# OUTL.net
KiCad netlist of a schematic drawn in Altium Designer
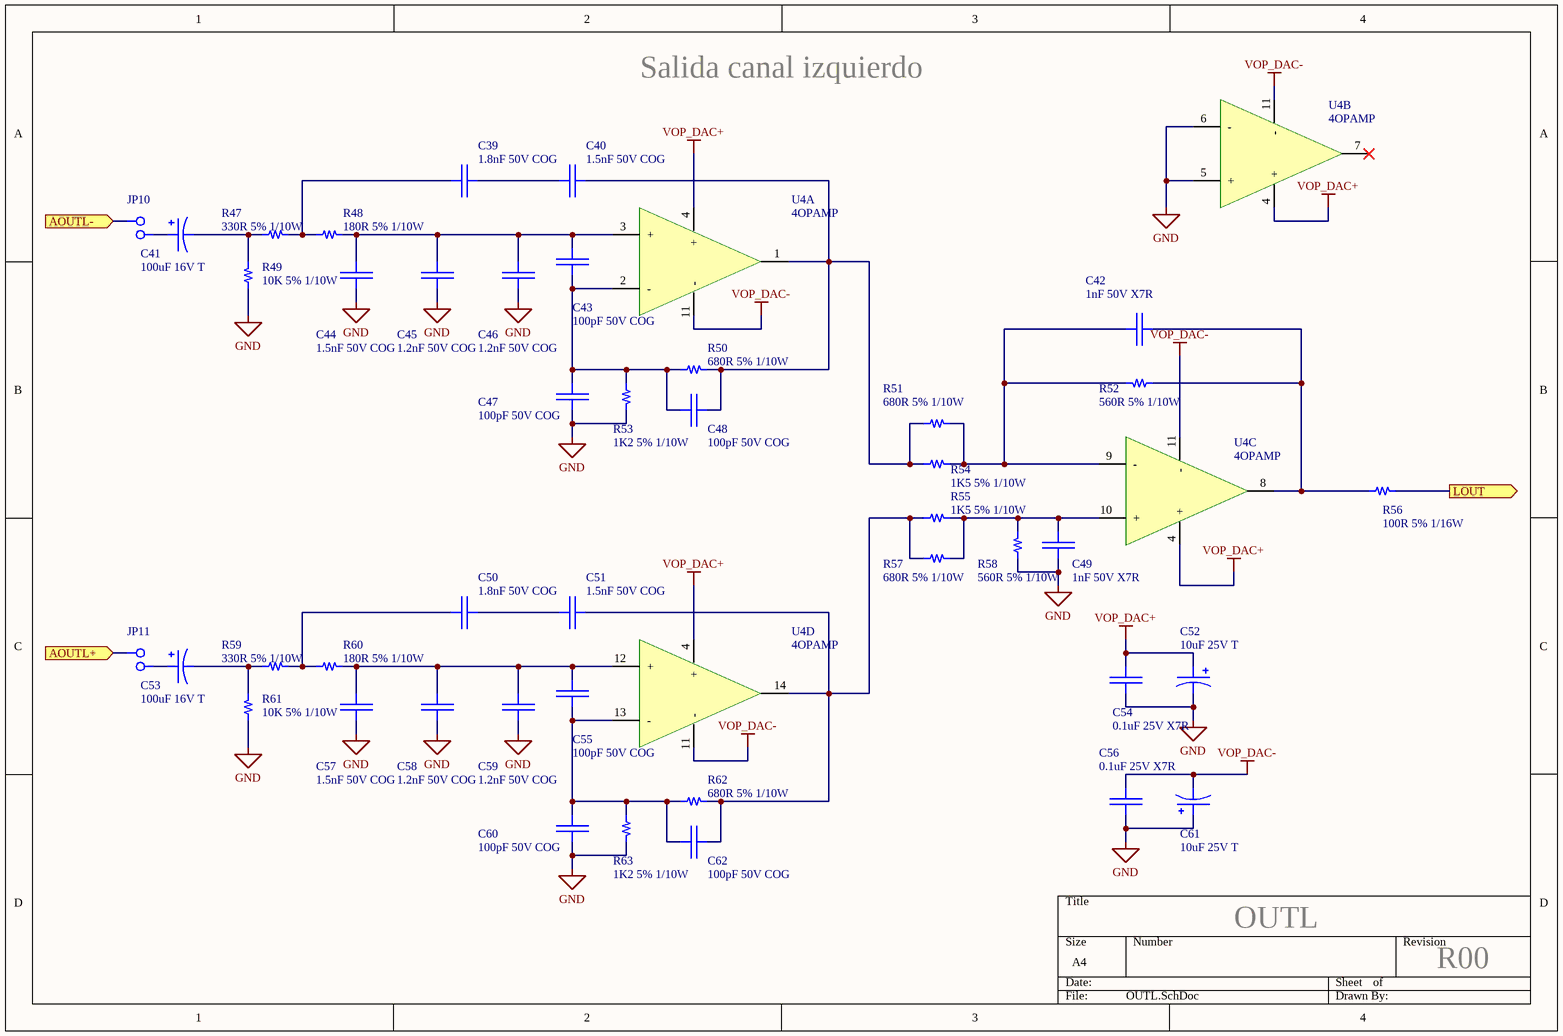
[diagram p0: OUTL.SchDoc]

(export (version "E")
  (design (tool "Eeschema 10.0.6"))
  (components
    (comp (ref "C39")
      (value "1.8nF 50V COG")
      (footprint "C_0805")
      (description "Capacitor de placas paralelas")
      (libsource (lib "Radios_Comunitarias") (part "Capacitor"))
    )
    (comp (ref "C40")
      (value "1.5nF 50V COG")
      (footprint "C_0805")
      (description "Capacitor de placas paralelas")
      (libsource (lib "Radios_Comunitarias") (part "Capacitor"))
    )
    (comp (ref "C41")
      (value "100uF 16V T")
      (footprint "TANT")
      (description "Capacitor polarizado")
      (libsource (lib "Radios_Comunitarias") (part "CapaPol"))
    )
    (comp (ref "C42")
      (value "1nF 50V X7R")
      (footprint "C_0805")
      (description "Capacitor de placas paralelas")
      (libsource (lib "Radios_Comunitarias") (part "Capacitor"))
    )
    (comp (ref "C43")
      (value "100pF 50V COG")
      (footprint "C_0805")
      (description "Capacitor de placas paralelas")
      (libsource (lib "Radios_Comunitarias") (part "Capacitor"))
    )
    (comp (ref "C44")
      (value "1.5nF 50V COG")
      (footprint "C_0805")
      (description "Capacitor de placas paralelas")
      (libsource (lib "Radios_Comunitarias") (part "Capacitor"))
    )
    (comp (ref "C45")
      (value "1.2nF 50V COG")
      (footprint "C_0805")
      (description "Capacitor de placas paralelas")
      (libsource (lib "Radios_Comunitarias") (part "Capacitor"))
    )
    (comp (ref "C46")
      (value "1.2nF 50V COG")
      (footprint "C_0805")
      (description "Capacitor de placas paralelas")
      (libsource (lib "Radios_Comunitarias") (part "Capacitor"))
    )
    (comp (ref "C47")
      (value "100pF 50V COG")
      (footprint "C_0805")
      (description "Capacitor de placas paralelas")
      (libsource (lib "Radios_Comunitarias") (part "Capacitor"))
    )
    (comp (ref "C48")
      (value "100pF 50V COG")
      (footprint "C_0805")
      (description "Capacitor de placas paralelas")
      (libsource (lib "Radios_Comunitarias") (part "Capacitor"))
    )
    (comp (ref "C49")
      (value "1nF 50V X7R")
      (footprint "C_0805")
      (description "Capacitor de placas paralelas")
      (libsource (lib "Radios_Comunitarias") (part "Capacitor"))
    )
    (comp (ref "C50")
      (value "1.8nF 50V COG")
      (footprint "C_0805")
      (description "Capacitor de placas paralelas")
      (libsource (lib "Radios_Comunitarias") (part "Capacitor"))
    )
    (comp (ref "C51")
      (value "1.5nF 50V COG")
      (footprint "C_0805")
      (description "Capacitor de placas paralelas")
      (libsource (lib "Radios_Comunitarias") (part "Capacitor"))
    )
    (comp (ref "C52")
      (value "10uF 25V T")
      (footprint "TANT")
      (description "Capacitor polarizado")
      (libsource (lib "") (part "CapaPol_1"))
    )
    (comp (ref "C53")
      (value "100uF 16V T")
      (footprint "TANT")
      (description "Capacitor polarizado")
      (libsource (lib "Radios_Comunitarias") (part "CapaPol"))
    )
    (comp (ref "C54")
      (value "0.1uF 25V X7R")
      (footprint "C_0805")
      (description "Capacitor de placas paralelas")
      (libsource (lib "Radios_Comunitarias") (part "Capacitor"))
    )
    (comp (ref "C55")
      (value "100pF 50V COG")
      (footprint "C_0805")
      (description "Capacitor de placas paralelas")
      (libsource (lib "Radios_Comunitarias") (part "Capacitor"))
    )
    (comp (ref "C56")
      (value "0.1uF 25V X7R")
      (footprint "C_0805")
      (description "Capacitor de placas paralelas")
      (libsource (lib "Radios_Comunitarias") (part "Capacitor"))
    )
    (comp (ref "C57")
      (value "1.5nF 50V COG")
      (footprint "C_0805")
      (description "Capacitor de placas paralelas")
      (libsource (lib "Radios_Comunitarias") (part "Capacitor"))
    )
    (comp (ref "C58")
      (value "1.2nF 50V COG")
      (footprint "C_0805")
      (description "Capacitor de placas paralelas")
      (libsource (lib "Radios_Comunitarias") (part "Capacitor"))
    )
    (comp (ref "C59")
      (value "1.2nF 50V COG")
      (footprint "C_0805")
      (description "Capacitor de placas paralelas")
      (libsource (lib "Radios_Comunitarias") (part "Capacitor"))
    )
    (comp (ref "C60")
      (value "100pF 50V COG")
      (footprint "C_0805")
      (description "Capacitor de placas paralelas")
      (libsource (lib "Radios_Comunitarias") (part "Capacitor"))
    )
    (comp (ref "C61")
      (value "10uF 25V T")
      (footprint "TANT")
      (description "Capacitor polarizado")
      (libsource (lib "") (part "CapaPol_1"))
    )
    (comp (ref "C62")
      (value "100pF 50V COG")
      (footprint "C_0805")
      (description "Capacitor de placas paralelas")
      (libsource (lib "Radios_Comunitarias") (part "Capacitor"))
    )
    (comp (ref "JP10")
      (value "Jumper 2x1")
      (footprint "Conn_2_1")
      (libsource (lib "Radios_Comunitarias") (part "Jumper 2x1"))
    )
    (comp (ref "JP11")
      (value "Jumper 2x1")
      (footprint "Conn_2_1")
      (libsource (lib "Radios_Comunitarias") (part "Jumper 2x1"))
    )
    (comp (ref "R47")
      (value "330R 5% 1/10W")
      (footprint "R_0805")
      (description "Resistencia")
      (libsource (lib "Radios_Comunitarias") (part "Resistor"))
    )
    (comp (ref "R48")
      (value "180R 5% 1/10W")
      (footprint "R_0805")
      (description "Resistencia")
      (libsource (lib "Radios_Comunitarias") (part "Resistor"))
    )
    (comp (ref "R49")
      (value "10K 5% 1/10W")
      (footprint "R_0805")
      (description "Resistencia")
      (libsource (lib "Radios_Comunitarias") (part "Resistor"))
    )
    (comp (ref "R50")
      (value "680R 5% 1/10W")
      (footprint "R_0805")
      (description "Resistencia")
      (libsource (lib "Radios_Comunitarias") (part "Resistor"))
    )
    (comp (ref "R51")
      (value "680R 5% 1/10W")
      (footprint "R_0805")
      (description "Resistencia")
      (libsource (lib "Radios_Comunitarias") (part "Resistor"))
    )
    (comp (ref "R52")
      (value "560R 5% 1/10W")
      (footprint "R_0805")
      (description "Resistencia")
      (libsource (lib "Radios_Comunitarias") (part "Resistor"))
    )
    (comp (ref "R53")
      (value "1K2 5% 1/10W")
      (footprint "R_0805")
      (description "Resistencia")
      (libsource (lib "Radios_Comunitarias") (part "Resistor"))
    )
    (comp (ref "R54")
      (value "1K5 5% 1/10W")
      (footprint "R_0805")
      (description "Resistencia")
      (libsource (lib "Radios_Comunitarias") (part "Resistor"))
    )
    (comp (ref "R55")
      (value "1K5 5% 1/10W")
      (footprint "R_0805")
      (description "Resistencia")
      (libsource (lib "Radios_Comunitarias") (part "Resistor"))
    )
    (comp (ref "R56")
      (value "100R 5% 1/16W")
      (footprint "R_0805")
      (description "Resistencia")
      (libsource (lib "Radios_Comunitarias") (part "Resistor"))
    )
    (comp (ref "R57")
      (value "680R 5% 1/10W")
      (footprint "R_0805")
      (description "Resistencia")
      (libsource (lib "Radios_Comunitarias") (part "Resistor"))
    )
    (comp (ref "R58")
      (value "560R 5% 1/10W")
      (footprint "R_0805")
      (description "Resistencia")
      (libsource (lib "Radios_Comunitarias") (part "Resistor"))
    )
    (comp (ref "R59")
      (value "330R 5% 1/10W")
      (footprint "R_0805")
      (description "Resistencia")
      (libsource (lib "Radios_Comunitarias") (part "Resistor"))
    )
    (comp (ref "R60")
      (value "180R 5% 1/10W")
      (footprint "R_0805")
      (description "Resistencia")
      (libsource (lib "Radios_Comunitarias") (part "Resistor"))
    )
    (comp (ref "R61")
      (value "10K 5% 1/10W")
      (footprint "R_0805")
      (description "Resistencia")
      (libsource (lib "Radios_Comunitarias") (part "Resistor"))
    )
    (comp (ref "R62")
      (value "680R 5% 1/10W")
      (footprint "R_0805")
      (description "Resistencia")
      (libsource (lib "Radios_Comunitarias") (part "Resistor"))
    )
    (comp (ref "R63")
      (value "1K2 5% 1/10W")
      (footprint "R_0805")
      (description "Resistencia")
      (libsource (lib "Radios_Comunitarias") (part "Resistor"))
    )
    (comp (ref "U4")
      (value "4OPAMP")
      (footprint "SOIC14")
      (description "Integrado con 4 operacionales")
      (libsource (lib "Radios_Comunitarias") (part "4OPAMP"))
    )
  )
  (nets
    (net (code "1") (name "/AOUTL+") (class "Default")
      (node (ref "JP11") (pin "1") (pinfunction "1_1") (pintype "passive"))
    )
    (net (code "2") (name "/AOUTL-") (class "Default")
      (node (ref "JP10") (pin "1") (pinfunction "1_1") (pintype "passive"))
    )
    (net (code "3") (name "/LOUT") (class "Default")
      (node (ref "R56") (pin "2") (pinfunction "2_2") (pintype "passive"))
    )
    (net (code "4") (name "GND") (class "Default")
      (node (ref "C44") (pin "1") (pinfunction "1_1") (pintype "passive"))
      (node (ref "C45") (pin "1") (pinfunction "1_1") (pintype "passive"))
      (node (ref "C46") (pin "1") (pinfunction "1_1") (pintype "passive"))
      (node (ref "C47") (pin "2") (pinfunction "2_2") (pintype "passive"))
      (node (ref "C49") (pin "2") (pinfunction "2_2") (pintype "passive"))
      (node (ref "C52") (pin "2") (pinfunction "2_2") (pintype "passive"))
      (node (ref "C54") (pin "2") (pinfunction "2_2") (pintype "passive"))
      (node (ref "C56") (pin "2") (pinfunction "2_2") (pintype "passive"))
      (node (ref "C57") (pin "1") (pinfunction "1_1") (pintype "passive"))
      (node (ref "C58") (pin "1") (pinfunction "1_1") (pintype "passive"))
      (node (ref "C59") (pin "1") (pinfunction "1_1") (pintype "passive"))
      (node (ref "C60") (pin "2") (pinfunction "2_2") (pintype "passive"))
      (node (ref "C61") (pin "1") (pinfunction "1_1") (pintype "passive"))
      (node (ref "R49") (pin "1") (pinfunction "1_1") (pintype "passive"))
      (node (ref "R53") (pin "2") (pinfunction "2_2") (pintype "passive"))
      (node (ref "R58") (pin "1") (pinfunction "1_1") (pintype "passive"))
      (node (ref "R61") (pin "1") (pinfunction "1_1") (pintype "passive"))
      (node (ref "R63") (pin "2") (pinfunction "2_2") (pintype "passive"))
      (node (ref "U4") (pin "5") (pinfunction "+_5") (pintype "passive"))
      (node (ref "U4") (pin "6") (pinfunction "-_6") (pintype "passive"))
    )
    (net (code "5") (name "Net-(C39-Pad1)") (class "Default")
      (node (ref "C39") (pin "1") (pinfunction "1_1") (pintype "passive"))
      (node (ref "C40") (pin "2") (pinfunction "2_2") (pintype "passive"))
    )
    (net (code "6") (name "Net-(C39-Pad2)") (class "Default")
      (node (ref "C39") (pin "2") (pinfunction "2_2") (pintype "passive"))
      (node (ref "R47") (pin "2") (pinfunction "2_2") (pintype "passive"))
      (node (ref "R48") (pin "1") (pinfunction "1_1") (pintype "passive"))
    )
    (net (code "7") (name "Net-(C41-Pad1)") (class "Default")
      (node (ref "C41") (pin "1") (pinfunction "1_1") (pintype "passive"))
      (node (ref "JP10") (pin "2") (pinfunction "2_2") (pintype "passive"))
    )
    (net (code "8") (name "Net-(C41-Pad2)") (class "Default")
      (node (ref "C41") (pin "2") (pinfunction "2_2") (pintype "passive"))
      (node (ref "R47") (pin "1") (pinfunction "1_1") (pintype "passive"))
      (node (ref "R49") (pin "2") (pinfunction "2_2") (pintype "passive"))
    )
    (net (code "9") (name "Net-(C42-Pad1)") (class "Default")
      (node (ref "C42") (pin "1") (pinfunction "1_1") (pintype "passive"))
      (node (ref "R51") (pin "2") (pinfunction "2_2") (pintype "passive"))
      (node (ref "R52") (pin "2") (pinfunction "2_2") (pintype "passive"))
      (node (ref "R54") (pin "2") (pinfunction "2_2") (pintype "passive"))
      (node (ref "U4") (pin "9") (pinfunction "-_9") (pintype "passive"))
    )
    (net (code "10") (name "Net-(C43-Pad1)") (class "Default")
      (node (ref "C43") (pin "1") (pinfunction "1_1") (pintype "passive"))
      (node (ref "C44") (pin "2") (pinfunction "2_2") (pintype "passive"))
      (node (ref "C45") (pin "2") (pinfunction "2_2") (pintype "passive"))
      (node (ref "C46") (pin "2") (pinfunction "2_2") (pintype "passive"))
      (node (ref "R48") (pin "2") (pinfunction "2_2") (pintype "passive"))
      (node (ref "U4") (pin "3") (pinfunction "+_3") (pintype "passive"))
    )
    (net (code "11") (name "Net-(C43-Pad2)") (class "Default")
      (node (ref "C43") (pin "2") (pinfunction "2_2") (pintype "passive"))
      (node (ref "C47") (pin "1") (pinfunction "1_1") (pintype "passive"))
      (node (ref "C48") (pin "1") (pinfunction "1_1") (pintype "passive"))
      (node (ref "R50") (pin "1") (pinfunction "1_1") (pintype "passive"))
      (node (ref "R53") (pin "1") (pinfunction "1_1") (pintype "passive"))
      (node (ref "U4") (pin "2") (pinfunction "-_2") (pintype "passive"))
    )
    (net (code "12") (name "Net-(C49-Pad1)") (class "Default")
      (node (ref "C49") (pin "1") (pinfunction "1_1") (pintype "passive"))
      (node (ref "R55") (pin "2") (pinfunction "2_2") (pintype "passive"))
      (node (ref "R57") (pin "2") (pinfunction "2_2") (pintype "passive"))
      (node (ref "R58") (pin "2") (pinfunction "2_2") (pintype "passive"))
      (node (ref "U4") (pin "10") (pinfunction "+_10") (pintype "passive"))
    )
    (net (code "13") (name "Net-(C50-Pad1)") (class "Default")
      (node (ref "C50") (pin "1") (pinfunction "1_1") (pintype "passive"))
      (node (ref "C51") (pin "2") (pinfunction "2_2") (pintype "passive"))
    )
    (net (code "14") (name "Net-(C50-Pad2)") (class "Default")
      (node (ref "C50") (pin "2") (pinfunction "2_2") (pintype "passive"))
      (node (ref "R59") (pin "2") (pinfunction "2_2") (pintype "passive"))
      (node (ref "R60") (pin "1") (pinfunction "1_1") (pintype "passive"))
    )
    (net (code "15") (name "Net-(C53-Pad1)") (class "Default")
      (node (ref "C53") (pin "1") (pinfunction "1_1") (pintype "passive"))
      (node (ref "JP11") (pin "2") (pinfunction "2_2") (pintype "passive"))
    )
    (net (code "16") (name "Net-(C53-Pad2)") (class "Default")
      (node (ref "C53") (pin "2") (pinfunction "2_2") (pintype "passive"))
      (node (ref "R59") (pin "1") (pinfunction "1_1") (pintype "passive"))
      (node (ref "R61") (pin "2") (pinfunction "2_2") (pintype "passive"))
    )
    (net (code "17") (name "Net-(C55-Pad1)") (class "Default")
      (node (ref "C55") (pin "1") (pinfunction "1_1") (pintype "passive"))
      (node (ref "C57") (pin "2") (pinfunction "2_2") (pintype "passive"))
      (node (ref "C58") (pin "2") (pinfunction "2_2") (pintype "passive"))
      (node (ref "C59") (pin "2") (pinfunction "2_2") (pintype "passive"))
      (node (ref "R60") (pin "2") (pinfunction "2_2") (pintype "passive"))
      (node (ref "U4") (pin "12") (pinfunction "+_12") (pintype "passive"))
    )
    (net (code "18") (name "Net-(C55-Pad2)") (class "Default")
      (node (ref "C55") (pin "2") (pinfunction "2_2") (pintype "passive"))
      (node (ref "C60") (pin "1") (pinfunction "1_1") (pintype "passive"))
      (node (ref "C62") (pin "1") (pinfunction "1_1") (pintype "passive"))
      (node (ref "R62") (pin "1") (pinfunction "1_1") (pintype "passive"))
      (node (ref "R63") (pin "1") (pinfunction "1_1") (pintype "passive"))
      (node (ref "U4") (pin "13") (pinfunction "-_13") (pintype "passive"))
    )
    (net (code "19") (name "Net-(U4A-OUT)") (class "Default")
      (node (ref "C40") (pin "1") (pinfunction "1_1") (pintype "passive"))
      (node (ref "C48") (pin "2") (pinfunction "2_2") (pintype "passive"))
      (node (ref "R50") (pin "2") (pinfunction "2_2") (pintype "passive"))
      (node (ref "R51") (pin "1") (pinfunction "1_1") (pintype "passive"))
      (node (ref "R54") (pin "1") (pinfunction "1_1") (pintype "passive"))
      (node (ref "U4") (pin "1") (pinfunction "OUT_1") (pintype "passive"))
    )
    (net (code "20") (name "Net-(U4C-OUT)") (class "Default")
      (node (ref "C42") (pin "2") (pinfunction "2_2") (pintype "passive"))
      (node (ref "R52") (pin "1") (pinfunction "1_1") (pintype "passive"))
      (node (ref "R56") (pin "1") (pinfunction "1_1") (pintype "passive"))
      (node (ref "U4") (pin "8") (pinfunction "OUT_8") (pintype "passive"))
    )
    (net (code "21") (name "Net-(U4D-OUT)") (class "Default")
      (node (ref "C51") (pin "1") (pinfunction "1_1") (pintype "passive"))
      (node (ref "C62") (pin "2") (pinfunction "2_2") (pintype "passive"))
      (node (ref "R55") (pin "1") (pinfunction "1_1") (pintype "passive"))
      (node (ref "R57") (pin "1") (pinfunction "1_1") (pintype "passive"))
      (node (ref "R62") (pin "2") (pinfunction "2_2") (pintype "passive"))
      (node (ref "U4") (pin "14") (pinfunction "OUT_14") (pintype "passive"))
    )
    (net (code "22") (name "VOP_DAC+") (class "Default")
      (node (ref "C52") (pin "1") (pinfunction "1_1") (pintype "passive"))
      (node (ref "C54") (pin "1") (pinfunction "1_1") (pintype "passive"))
      (node (ref "U4") (pin "4") (pinfunction "+_4") (pintype "power_in"))
    )
    (net (code "23") (name "VOP_DAC-") (class "Default")
      (node (ref "C56") (pin "1") (pinfunction "1_1") (pintype "passive"))
      (node (ref "C61") (pin "2") (pinfunction "2_2") (pintype "passive"))
      (node (ref "U4") (pin "11") (pinfunction "-_11") (pintype "passive"))
    )
    (net (code "24") (name "unconnected-(U4B-OUT-Pad7)") (class "Default")
      (node (ref "U4") (pin "7") (pinfunction "OUT_7") (pintype "passive+no_connect"))
    )
  )
)
